# main.net
KiCad netlist of a schematic drawn in EAGLE
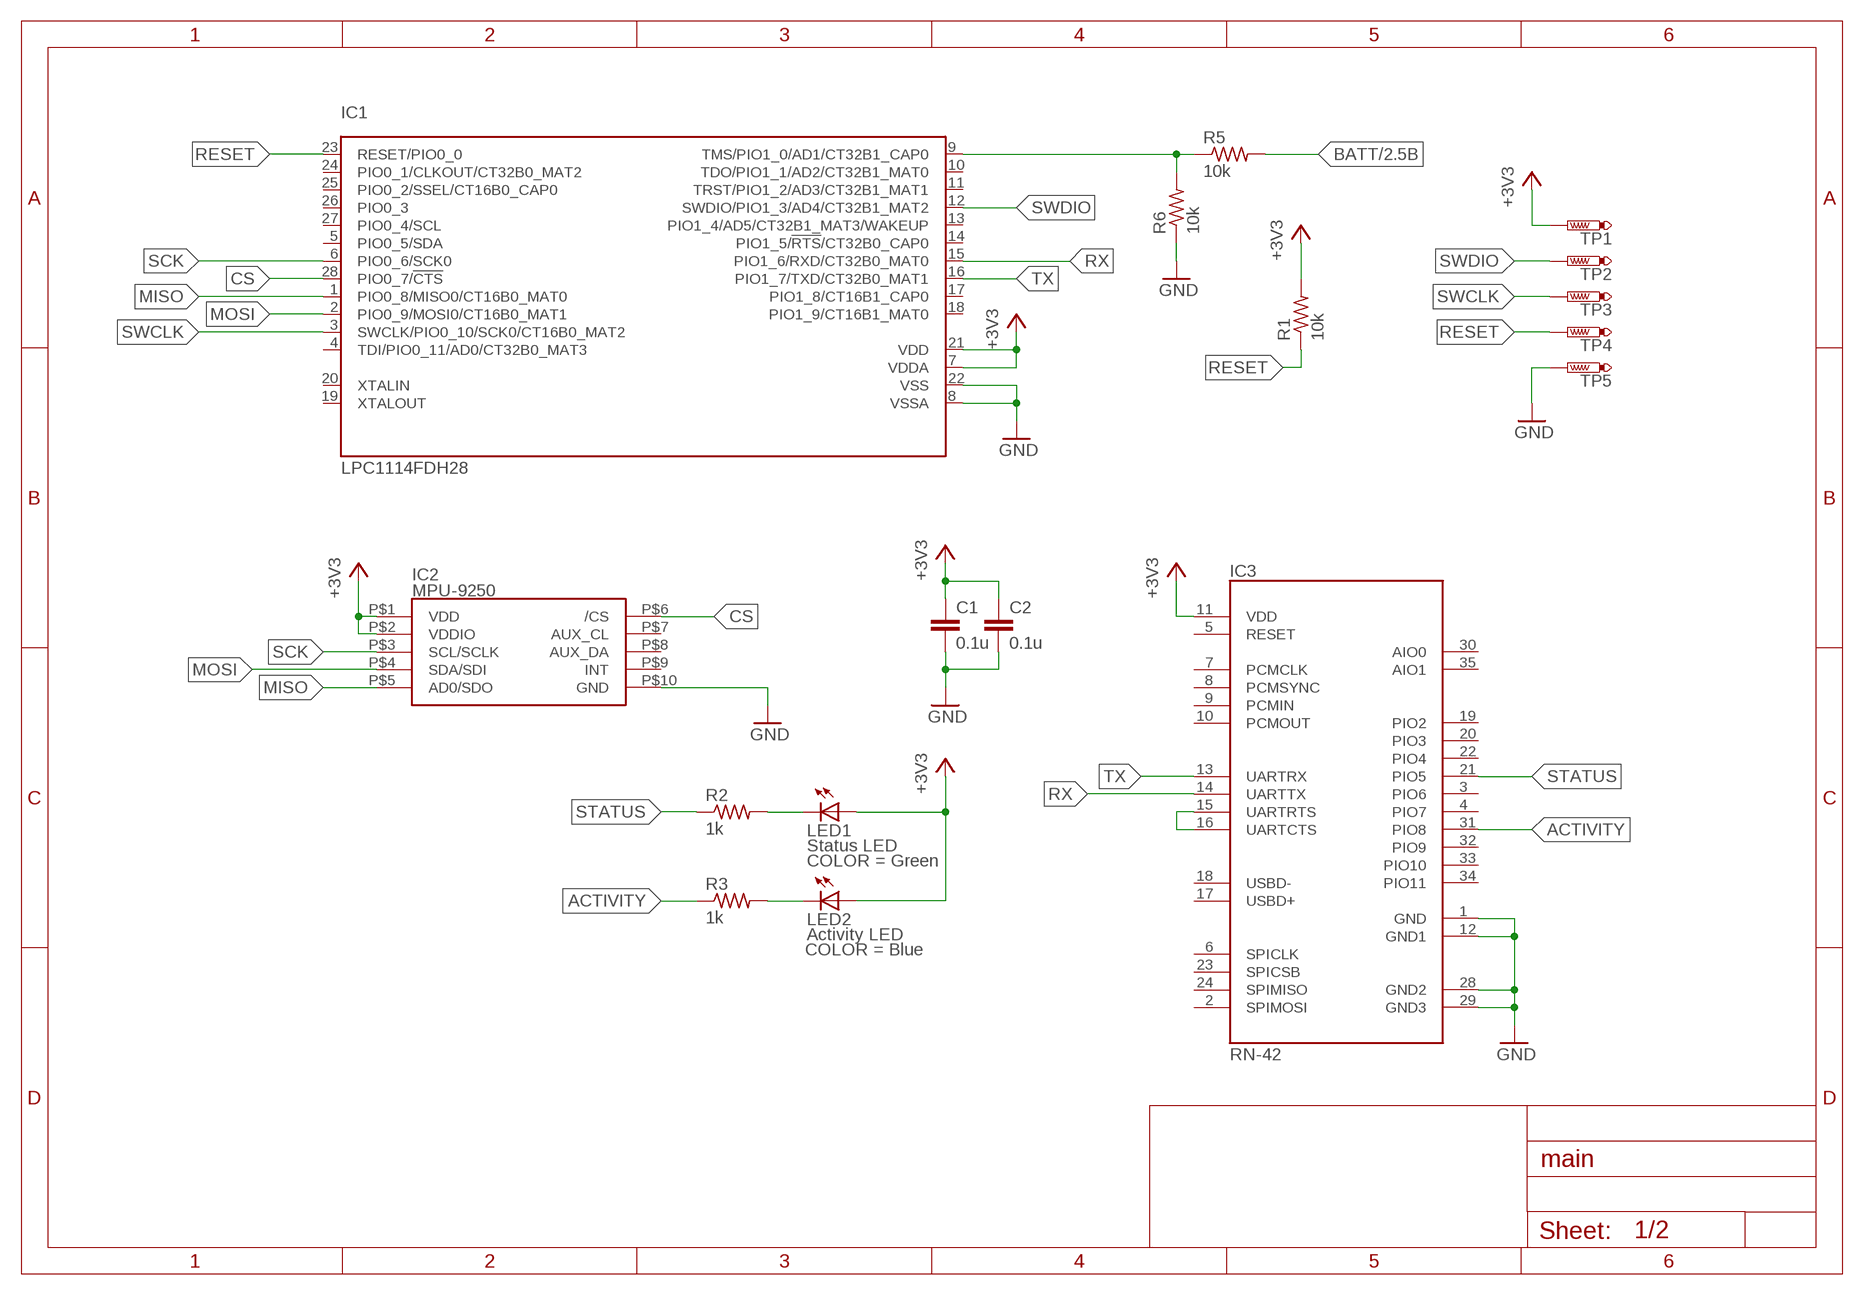
[diagram p0: schematic, sheet 1]
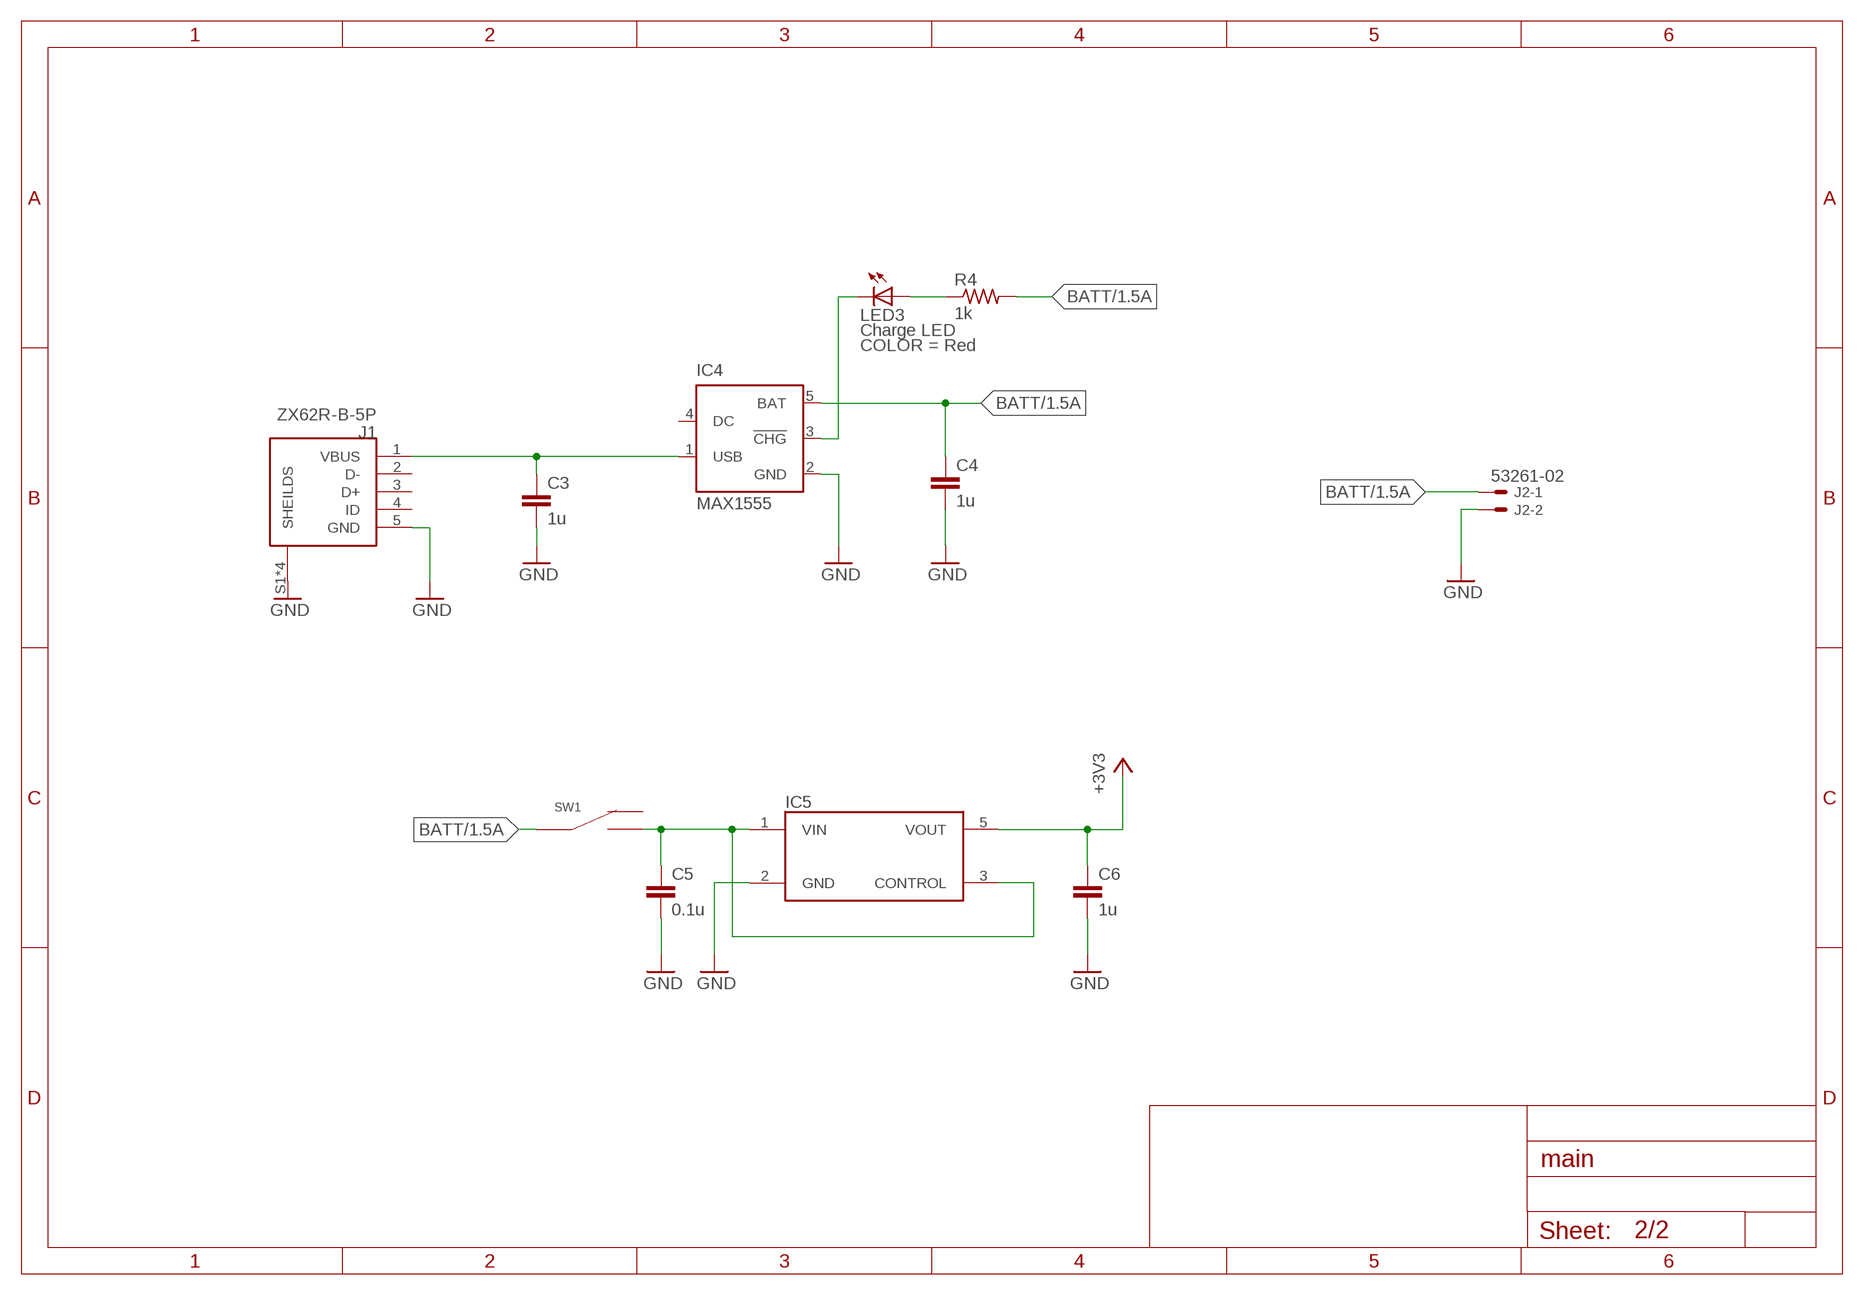
[diagram p1: schematic, sheet 2]

(export (version "E")
  (design (tool "Eeschema 10.0.6"))
  (components
    (comp (ref "C3")
      (value "1u")
      (footprint "eagle-import:C0603")
      (libsource (lib "eagle-import") (part "C-EUC0603"))
    )
    (comp (ref "C4")
      (value "1u")
      (footprint "eagle-import:C0603")
      (libsource (lib "eagle-import") (part "C-EUC0603"))
    )
    (comp (ref "C5")
      (value "0.1u")
      (footprint "eagle-import:C0603")
      (libsource (lib "eagle-import") (part "C-EUC0603"))
    )
    (comp (ref "C6")
      (value "1u")
      (footprint "eagle-import:C0603")
      (libsource (lib "eagle-import") (part "C-EUC0603"))
    )
    (comp (ref "IC4")
      (value "MAX1555")
      (footprint "eagle-import:SOT23-5L")
      (fields (field (name "MF") "MAXIM") (field (name "MPN") "MAX1555EZK+T"))
      (libsource (lib "eagle-import") (part "MAX1555"))
    )
    (comp (ref "IC5")
      (value "NJM2866F33")
      (footprint "eagle-import:SOT23-5L")
      (fields (field (name "MF") "NewJRC"))
      (libsource (lib "eagle-import") (part "NJM2866F33"))
    )
    (comp (ref "J1")
      (value "ZX62R-B-5P")
      (footprint "eagle-import:ZX62R-B-5P")
      (fields (field (name "MF") "Hirose"))
      (libsource (lib "eagle-import") (part "ZX62R-B-5P"))
    )
    (comp (ref "J2")
      (value "53261-02")
      (footprint "eagle-import:53261-02")
      (fields
        (field (name "MF") "Molex")
        (field (name "MPN") "53261-0271")
        (field (name "OC") "542-7090")
        (field (name "SITE") "RS Components")
      )
      (libsource (lib "eagle-import") (part "53?-02261"))
    )
    (comp (ref "LED3")
      (value "Charge LED")
      (footprint "eagle-import:CHIP-LED0603")
      (fields
        (field (name "COLOR") "Red")
        (field (name "MF") "OptoSupply")
        (field (name "MPN") "OSHR1608C1A")
      )
      (libsource (lib "eagle-import") (part "LEDCHIP-LED0603"))
    )
    (comp (ref "R4")
      (value "1k")
      (footprint "eagle-import:R0603")
      (libsource (lib "eagle-import") (part "R-US_R0603"))
    )
    (comp (ref "SW1")
      (value "SK-12D01-VG4")
      (footprint "eagle-import:SK-12D01-VG4")
      (fields (field (name "MF") "Zhejiang Jianfu"))
      (libsource (lib "eagle-import") (part "SK-12D01-VG4"))
    )
    (comp (ref "C1")
      (value "0.1u")
      (footprint "eagle-import:C0603")
      (libsource (lib "eagle-import") (part "C-EUC0603"))
    )
    (comp (ref "C2")
      (value "0.1u")
      (footprint "eagle-import:C0603")
      (libsource (lib "eagle-import") (part "C-EUC0603"))
    )
    (comp (ref "IC1")
      (value "LPC1114FDH28")
      (footprint "eagle-import:SOT361-1")
      (fields (field (name "MF") "NXP Semiconductors") (field (name "MPN") "LPC1114FDH28/102"))
      (libsource (lib "eagle-import") (part "LPC1114FDH28"))
    )
    (comp (ref "IC2")
      (value "MPU-9250")
      (footprint "eagle-import:DIP10S")
      (fields (field (name "MF") "InverSense"))
      (libsource (lib "eagle-import") (part "MPU-9250"))
    )
    (comp (ref "IC3")
      (value "RN-42")
      (footprint "eagle-import:RN41")
      (fields (field (name "MF") "Microchip") (field (name "MPN") "RN-42-I/RM"))
      (libsource (lib "eagle-import") (part "BLUETOOTH-RN41{dblquote}"))
    )
    (comp (ref "LED1")
      (value "Status LED")
      (footprint "eagle-import:CHIP-LED0603")
      (fields
        (field (name "COLOR") "Green")
        (field (name "MF") "OptoSupply")
        (field (name "MPN") "OSYG1608C1A")
      )
      (libsource (lib "eagle-import") (part "LEDCHIP-LED0603"))
    )
    (comp (ref "LED2")
      (value "Activity LED")
      (footprint "eagle-import:CHIP-LED0603")
      (fields
        (field (name "COLOR") "Blue")
        (field (name "MF") "OptoSupply")
        (field (name "MPN") "OSBL1608C1A")
      )
      (libsource (lib "eagle-import") (part "LEDCHIP-LED0603"))
    )
    (comp (ref "R1")
      (value "10k")
      (footprint "eagle-import:R0603")
      (libsource (lib "eagle-import") (part "R-US_R0603"))
    )
    (comp (ref "R2")
      (value "1k")
      (footprint "eagle-import:R0603")
      (libsource (lib "eagle-import") (part "R-US_R0603"))
    )
    (comp (ref "R3")
      (value "1k")
      (footprint "eagle-import:R0603")
      (libsource (lib "eagle-import") (part "R-US_R0603"))
    )
    (comp (ref "R5")
      (value "10k")
      (footprint "eagle-import:R0603")
      (libsource (lib "eagle-import") (part "R-US_R0603"))
    )
    (comp (ref "R6")
      (value "10k")
      (footprint "eagle-import:R0603")
      (libsource (lib "eagle-import") (part "R-US_R0603"))
    )
    (comp (ref "TP1")
      (value "3V3")
      (footprint "eagle-import:B1,27")
      (libsource (lib "eagle-import") (part "PTR1B1,27"))
    )
    (comp (ref "TP2")
      (value "SWDIO")
      (footprint "eagle-import:B1,27")
      (libsource (lib "eagle-import") (part "PTR1B1,27"))
    )
    (comp (ref "TP3")
      (value "SWCLK")
      (footprint "eagle-import:B1,27")
      (libsource (lib "eagle-import") (part "PTR1B1,27"))
    )
    (comp (ref "TP4")
      (value "RESET")
      (footprint "eagle-import:B1,27")
      (libsource (lib "eagle-import") (part "PTR1B1,27"))
    )
    (comp (ref "TP5")
      (value "GND")
      (footprint "eagle-import:B1,27")
      (libsource (lib "eagle-import") (part "PTR1B1,27"))
    )
  )
  (nets
    (net (code "1") (name "+3V3") (class "Default")
      (node (ref "C1") (pin "1") (pinfunction "1_1") (pintype "passive"))
      (node (ref "C2") (pin "1") (pinfunction "1_1") (pintype "passive"))
      (node (ref "C6") (pin "1") (pinfunction "1_1") (pintype "passive"))
      (node (ref "IC1") (pin "21") (pinfunction "VDD_21") (pintype "power_in"))
      (node (ref "IC1") (pin "7") (pinfunction "VDDA_7") (pintype "power_in"))
      (node (ref "IC2") (pin "P$1") (pinfunction "VDD_P$1") (pintype "bidirectional"))
      (node (ref "IC2") (pin "P$2") (pinfunction "VDDIO_P$2") (pintype "bidirectional"))
      (node (ref "IC3") (pin "11") (pinfunction "VDD_11") (pintype "bidirectional"))
      (node (ref "IC5") (pin "5") (pinfunction "VOUT_5") (pintype "bidirectional"))
      (node (ref "LED1") (pin "A") (pinfunction "A_A") (pintype "passive"))
      (node (ref "LED2") (pin "A") (pinfunction "A_A") (pintype "passive"))
      (node (ref "R1") (pin "2") (pinfunction "2_2") (pintype "passive"))
      (node (ref "TP1") (pin "TP") (pinfunction "TP_TP") (pintype "input"))
    )
    (net (code "2") (name "ACTIVITY") (class "Default")
      (node (ref "IC3") (pin "31") (pinfunction "PIO8_31") (pintype "bidirectional"))
      (node (ref "R3") (pin "1") (pinfunction "1_1") (pintype "passive"))
    )
    (net (code "3") (name "BATT") (class "Default")
      (node (ref "C4") (pin "1") (pinfunction "1_1") (pintype "passive"))
      (node (ref "IC4") (pin "5") (pinfunction "BAT_5") (pintype "passive"))
      (node (ref "J2") (pin "1") (pinfunction "S_1") (pintype "passive"))
      (node (ref "R4") (pin "2") (pinfunction "2_2") (pintype "passive"))
      (node (ref "R5") (pin "2") (pinfunction "2_2") (pintype "passive"))
      (node (ref "SW1") (pin "P$2") (pinfunction "P$1_P$2") (pintype "bidirectional"))
    )
    (net (code "4") (name "CS") (class "Default")
      (node (ref "IC1") (pin "28") (pinfunction "PIO0_7/~{CTS}_28") (pintype "bidirectional"))
      (node (ref "IC2") (pin "P$6") (pinfunction "/CS_P$6") (pintype "bidirectional"))
    )
    (net (code "5") (name "GND") (class "Default")
      (node (ref "C1") (pin "2") (pinfunction "2_2") (pintype "passive"))
      (node (ref "C2") (pin "2") (pinfunction "2_2") (pintype "passive"))
      (node (ref "C3") (pin "2") (pinfunction "2_2") (pintype "passive"))
      (node (ref "C4") (pin "2") (pinfunction "2_2") (pintype "passive"))
      (node (ref "C5") (pin "2") (pinfunction "2_2") (pintype "passive"))
      (node (ref "C6") (pin "2") (pinfunction "2_2") (pintype "passive"))
      (node (ref "IC1") (pin "22") (pinfunction "VSS_22") (pintype "power_in"))
      (node (ref "IC1") (pin "8") (pinfunction "VSSA_8") (pintype "power_in"))
      (node (ref "IC2") (pin "P$10") (pinfunction "GND_P$10") (pintype "bidirectional"))
      (node (ref "IC3") (pin "1") (pinfunction "GND_1") (pintype "bidirectional"))
      (node (ref "IC3") (pin "12") (pinfunction "GND1_12") (pintype "bidirectional"))
      (node (ref "IC3") (pin "28") (pinfunction "GND2_28") (pintype "bidirectional"))
      (node (ref "IC3") (pin "29") (pinfunction "GND3_29") (pintype "bidirectional"))
      (node (ref "IC4") (pin "2") (pinfunction "GND_2") (pintype "power_in"))
      (node (ref "IC5") (pin "2") (pinfunction "GND_2") (pintype "bidirectional"))
      (node (ref "J1") (pin "5") (pinfunction "GND_5") (pintype "bidirectional"))
      (node (ref "J1") (pin "S1") (pinfunction "SHEILDS_S1") (pintype "bidirectional"))
      (node (ref "J1") (pin "S2") (pinfunction "SHEILDS_S2") (pintype "bidirectional"))
      (node (ref "J1") (pin "S3") (pinfunction "SHEILDS_S3") (pintype "bidirectional"))
      (node (ref "J1") (pin "S4") (pinfunction "SHEILDS_S4") (pintype "bidirectional"))
      (node (ref "J2") (pin "2") (pinfunction "S_2") (pintype "passive"))
      (node (ref "R6") (pin "1") (pinfunction "1_1") (pintype "passive"))
      (node (ref "TP5") (pin "TP") (pinfunction "TP_TP") (pintype "input"))
    )
    (net (code "6") (name "MISO") (class "Default")
      (node (ref "IC1") (pin "1") (pinfunction "PIO0_8/MISO0/CT16B0_MAT0_1") (pintype "bidirectional"))
      (node (ref "IC2") (pin "P$5") (pinfunction "AD0/SDO_P$5") (pintype "bidirectional"))
    )
    (net (code "7") (name "MOSI") (class "Default")
      (node (ref "IC1") (pin "2") (pinfunction "PIO0_9/MOSI0/CT16B0_MAT1_2") (pintype "bidirectional"))
      (node (ref "IC2") (pin "P$4") (pinfunction "SDA/SDI_P$4") (pintype "bidirectional"))
    )
    (net (code "8") (name "Net-(IC1-TMS{slash}PIO1_0{slash}AD1{slash}CT32B1_CAP0)") (class "Default")
      (node (ref "IC1") (pin "9") (pinfunction "TMS/PIO1_0/AD1/CT32B1_CAP0_9") (pintype "bidirectional"))
      (node (ref "R5") (pin "1") (pinfunction "1_1") (pintype "passive"))
      (node (ref "R6") (pin "2") (pinfunction "2_2") (pintype "passive"))
    )
    (net (code "9") (name "Net-(IC3-UARTCTS)") (class "Default")
      (node (ref "IC3") (pin "15") (pinfunction "UARTRTS_15") (pintype "bidirectional"))
      (node (ref "IC3") (pin "16") (pinfunction "UARTCTS_16") (pintype "bidirectional"))
    )
    (net (code "10") (name "Net-(IC4-USB)") (class "Default")
      (node (ref "C3") (pin "1") (pinfunction "1_1") (pintype "passive"))
      (node (ref "IC4") (pin "1") (pinfunction "USB_1") (pintype "input"))
      (node (ref "J1") (pin "1") (pinfunction "VBUS_1") (pintype "bidirectional"))
    )
    (net (code "11") (name "Net-(IC4-~{CHG})") (class "Default")
      (node (ref "IC4") (pin "3") (pinfunction "~{CHG}_3") (pintype "output"))
      (node (ref "LED3") (pin "C") (pinfunction "C_C") (pintype "passive"))
    )
    (net (code "12") (name "Net-(IC5-CONTROL)") (class "Default")
      (node (ref "C5") (pin "1") (pinfunction "1_1") (pintype "passive"))
      (node (ref "IC5") (pin "1") (pinfunction "VIN_1") (pintype "bidirectional"))
      (node (ref "IC5") (pin "3") (pinfunction "CONTROL_3") (pintype "bidirectional"))
      (node (ref "SW1") (pin "P$3") (pinfunction "P$3_P$3") (pintype "bidirectional"))
    )
    (net (code "13") (name "Net-(LED1-PadC)") (class "Default")
      (node (ref "LED1") (pin "C") (pinfunction "C_C") (pintype "passive"))
      (node (ref "R2") (pin "2") (pinfunction "2_2") (pintype "passive"))
    )
    (net (code "14") (name "Net-(LED2-PadC)") (class "Default")
      (node (ref "LED2") (pin "C") (pinfunction "C_C") (pintype "passive"))
      (node (ref "R3") (pin "2") (pinfunction "2_2") (pintype "passive"))
    )
    (net (code "15") (name "Net-(LED3-PadA)") (class "Default")
      (node (ref "LED3") (pin "A") (pinfunction "A_A") (pintype "passive"))
      (node (ref "R4") (pin "1") (pinfunction "1_1") (pintype "passive"))
    )
    (net (code "16") (name "RESET") (class "Default")
      (node (ref "IC1") (pin "23") (pinfunction "RESET/PIO0_0_23") (pintype "bidirectional"))
      (node (ref "R1") (pin "1") (pinfunction "1_1") (pintype "passive"))
      (node (ref "TP4") (pin "TP") (pinfunction "TP_TP") (pintype "input"))
    )
    (net (code "17") (name "RX") (class "Default")
      (node (ref "IC1") (pin "15") (pinfunction "PIO1_6/RXD/CT32B0_MAT0_15") (pintype "bidirectional"))
      (node (ref "IC3") (pin "14") (pinfunction "UARTTX_14") (pintype "bidirectional"))
    )
    (net (code "18") (name "SCK") (class "Default")
      (node (ref "IC1") (pin "6") (pinfunction "PIO0_6/SCK0_6") (pintype "bidirectional"))
      (node (ref "IC2") (pin "P$3") (pinfunction "SCL/SCLK_P$3") (pintype "bidirectional"))
    )
    (net (code "19") (name "STATUS") (class "Default")
      (node (ref "IC3") (pin "21") (pinfunction "PIO5_21") (pintype "bidirectional"))
      (node (ref "R2") (pin "1") (pinfunction "1_1") (pintype "passive"))
    )
    (net (code "20") (name "SWCLK") (class "Default")
      (node (ref "IC1") (pin "3") (pinfunction "SWCLK/PIO0_10/SCK0/CT16B0_MAT2_3") (pintype "bidirectional"))
      (node (ref "TP3") (pin "TP") (pinfunction "TP_TP") (pintype "input"))
    )
    (net (code "21") (name "SWDIO") (class "Default")
      (node (ref "IC1") (pin "12") (pinfunction "SWDIO/PIO1_3/AD4/CT32B1_MAT2_12") (pintype "bidirectional"))
      (node (ref "TP2") (pin "TP") (pinfunction "TP_TP") (pintype "input"))
    )
    (net (code "22") (name "TX") (class "Default")
      (node (ref "IC1") (pin "16") (pinfunction "PIO1_7/TXD/CT32B0_MAT1_16") (pintype "bidirectional"))
      (node (ref "IC3") (pin "13") (pinfunction "UARTRX_13") (pintype "bidirectional"))
    )
    (net (code "23") (name "unconnected-(IC1-PIO0_1{slash}CLKOUT{slash}CT32B0_MAT2-Pad24)") (class "Default")
      (node (ref "IC1") (pin "24") (pinfunction "PIO0_1/CLKOUT/CT32B0_MAT2_24") (pintype "bidirectional"))
    )
    (net (code "24") (name "unconnected-(IC1-PIO0_2{slash}SSEL{slash}CT16B0_CAP0-Pad25)") (class "Default")
      (node (ref "IC1") (pin "25") (pinfunction "PIO0_2/SSEL/CT16B0_CAP0_25") (pintype "bidirectional"))
    )
    (net (code "25") (name "unconnected-(IC1-PIO0_3-Pad26)") (class "Default")
      (node (ref "IC1") (pin "26") (pinfunction "PIO0_3_26") (pintype "bidirectional"))
    )
    (net (code "26") (name "unconnected-(IC1-PIO0_4{slash}SCL-Pad27)") (class "Default")
      (node (ref "IC1") (pin "27") (pinfunction "PIO0_4/SCL_27") (pintype "bidirectional"))
    )
    (net (code "27") (name "unconnected-(IC1-PIO0_5{slash}SDA-Pad5)") (class "Default")
      (node (ref "IC1") (pin "5") (pinfunction "PIO0_5/SDA_5") (pintype "bidirectional"))
    )
    (net (code "28") (name "unconnected-(IC1-PIO1_4{slash}AD5{slash}CT32B1_MAT3{slash}WAKEUP-Pad13)") (class "Default")
      (node (ref "IC1") (pin "13") (pinfunction "PIO1_4/AD5/CT32B1_MAT3/WAKEUP_13") (pintype "bidirectional"))
    )
    (net (code "29") (name "unconnected-(IC1-PIO1_5{slash}~{RTS}{slash}CT32B0_CAP0-Pad14)") (class "Default")
      (node (ref "IC1") (pin "14") (pinfunction "PIO1_5/~{RTS}/CT32B0_CAP0_14") (pintype "bidirectional"))
    )
    (net (code "30") (name "unconnected-(IC1-PIO1_8{slash}CT16B1_CAP0-Pad17)") (class "Default")
      (node (ref "IC1") (pin "17") (pinfunction "PIO1_8/CT16B1_CAP0_17") (pintype "bidirectional"))
    )
    (net (code "31") (name "unconnected-(IC1-PIO1_9{slash}CT16B1_MAT0-Pad18)") (class "Default")
      (node (ref "IC1") (pin "18") (pinfunction "PIO1_9/CT16B1_MAT0_18") (pintype "bidirectional"))
    )
    (net (code "32") (name "unconnected-(IC1-TDI{slash}PIO0_11{slash}AD0{slash}CT32B0_MAT3-Pad4)") (class "Default")
      (node (ref "IC1") (pin "4") (pinfunction "TDI/PIO0_11/AD0/CT32B0_MAT3_4") (pintype "bidirectional"))
    )
    (net (code "33") (name "unconnected-(IC1-TDO{slash}PIO1_1{slash}AD2{slash}CT32B1_MAT0-Pad10)") (class "Default")
      (node (ref "IC1") (pin "10") (pinfunction "TDO/PIO1_1/AD2/CT32B1_MAT0_10") (pintype "bidirectional"))
    )
    (net (code "34") (name "unconnected-(IC1-TRST{slash}PIO1_2{slash}AD3{slash}CT32B1_MAT1-Pad11)") (class "Default")
      (node (ref "IC1") (pin "11") (pinfunction "TRST/PIO1_2/AD3/CT32B1_MAT1_11") (pintype "bidirectional"))
    )
    (net (code "35") (name "unconnected-(IC1-XTALIN-Pad20)") (class "Default")
      (node (ref "IC1") (pin "20") (pinfunction "XTALIN_20") (pintype "input"))
    )
    (net (code "36") (name "unconnected-(IC1-XTALOUT-Pad19)") (class "Default")
      (node (ref "IC1") (pin "19") (pinfunction "XTALOUT_19") (pintype "output"))
    )
    (net (code "37") (name "unconnected-(IC2-AUX_CL-PadP$7)") (class "Default")
      (node (ref "IC2") (pin "P$7") (pinfunction "AUX_CL_P$7") (pintype "bidirectional"))
    )
    (net (code "38") (name "unconnected-(IC2-AUX_DA-PadP$8)") (class "Default")
      (node (ref "IC2") (pin "P$8") (pinfunction "AUX_DA_P$8") (pintype "bidirectional"))
    )
    (net (code "39") (name "unconnected-(IC2-INT-PadP$9)") (class "Default")
      (node (ref "IC2") (pin "P$9") (pinfunction "INT_P$9") (pintype "bidirectional"))
    )
    (net (code "40") (name "unconnected-(IC3-AIO0-Pad30)") (class "Default")
      (node (ref "IC3") (pin "30") (pinfunction "AIO0_30") (pintype "bidirectional"))
    )
    (net (code "41") (name "unconnected-(IC3-AIO1-Pad35)") (class "Default")
      (node (ref "IC3") (pin "35") (pinfunction "AIO1_35") (pintype "bidirectional"))
    )
    (net (code "42") (name "unconnected-(IC3-PCMCLK-Pad7)") (class "Default")
      (node (ref "IC3") (pin "7") (pinfunction "PCMCLK_7") (pintype "bidirectional"))
    )
    (net (code "43") (name "unconnected-(IC3-PCMIN-Pad9)") (class "Default")
      (node (ref "IC3") (pin "9") (pinfunction "PCMIN_9") (pintype "bidirectional"))
    )
    (net (code "44") (name "unconnected-(IC3-PCMOUT-Pad10)") (class "Default")
      (node (ref "IC3") (pin "10") (pinfunction "PCMOUT_10") (pintype "bidirectional"))
    )
    (net (code "45") (name "unconnected-(IC3-PCMSYNC-Pad8)") (class "Default")
      (node (ref "IC3") (pin "8") (pinfunction "PCMSYNC_8") (pintype "bidirectional"))
    )
    (net (code "46") (name "unconnected-(IC3-PIO2-Pad19)") (class "Default")
      (node (ref "IC3") (pin "19") (pinfunction "PIO2_19") (pintype "bidirectional"))
    )
    (net (code "47") (name "unconnected-(IC3-PIO3-Pad20)") (class "Default")
      (node (ref "IC3") (pin "20") (pinfunction "PIO3_20") (pintype "bidirectional"))
    )
    (net (code "48") (name "unconnected-(IC3-PIO4-Pad22)") (class "Default")
      (node (ref "IC3") (pin "22") (pinfunction "PIO4_22") (pintype "bidirectional"))
    )
    (net (code "49") (name "unconnected-(IC3-PIO6-Pad3)") (class "Default")
      (node (ref "IC3") (pin "3") (pinfunction "PIO6_3") (pintype "bidirectional"))
    )
    (net (code "50") (name "unconnected-(IC3-PIO7-Pad4)") (class "Default")
      (node (ref "IC3") (pin "4") (pinfunction "PIO7_4") (pintype "bidirectional"))
    )
    (net (code "51") (name "unconnected-(IC3-PIO9-Pad32)") (class "Default")
      (node (ref "IC3") (pin "32") (pinfunction "PIO9_32") (pintype "bidirectional"))
    )
    (net (code "52") (name "unconnected-(IC3-PIO10-Pad33)") (class "Default")
      (node (ref "IC3") (pin "33") (pinfunction "PIO10_33") (pintype "bidirectional"))
    )
    (net (code "53") (name "unconnected-(IC3-PIO11-Pad34)") (class "Default")
      (node (ref "IC3") (pin "34") (pinfunction "PIO11_34") (pintype "bidirectional"))
    )
    (net (code "54") (name "unconnected-(IC3-RESET-Pad5)") (class "Default")
      (node (ref "IC3") (pin "5") (pinfunction "RESET_5") (pintype "bidirectional"))
    )
    (net (code "55") (name "unconnected-(IC3-SPICLK-Pad6)") (class "Default")
      (node (ref "IC3") (pin "6") (pinfunction "SPICLK_6") (pintype "bidirectional"))
    )
    (net (code "56") (name "unconnected-(IC3-SPICSB-Pad23)") (class "Default")
      (node (ref "IC3") (pin "23") (pinfunction "SPICSB_23") (pintype "bidirectional"))
    )
    (net (code "57") (name "unconnected-(IC3-SPIMISO-Pad24)") (class "Default")
      (node (ref "IC3") (pin "24") (pinfunction "SPIMISO_24") (pintype "bidirectional"))
    )
    (net (code "58") (name "unconnected-(IC3-SPIMOSI-Pad2)") (class "Default")
      (node (ref "IC3") (pin "2") (pinfunction "SPIMOSI_2") (pintype "bidirectional"))
    )
    (net (code "59") (name "unconnected-(IC3-USBD+-Pad17)") (class "Default")
      (node (ref "IC3") (pin "17") (pinfunction "USBD+_17") (pintype "bidirectional"))
    )
    (net (code "60") (name "unconnected-(IC3-USBD--Pad18)") (class "Default")
      (node (ref "IC3") (pin "18") (pinfunction "USBD-_18") (pintype "bidirectional"))
    )
    (net (code "61") (name "unconnected-(IC4-DC-Pad4)") (class "Default")
      (node (ref "IC4") (pin "4") (pinfunction "DC_4") (pintype "input"))
    )
    (net (code "62") (name "unconnected-(J1-D+-Pad3)") (class "Default")
      (node (ref "J1") (pin "3") (pinfunction "D+_3") (pintype "bidirectional"))
    )
    (net (code "63") (name "unconnected-(J1-D--Pad2)") (class "Default")
      (node (ref "J1") (pin "2") (pinfunction "D-_2") (pintype "bidirectional"))
    )
    (net (code "64") (name "unconnected-(J1-ID-Pad4)") (class "Default")
      (node (ref "J1") (pin "4") (pinfunction "ID_4") (pintype "bidirectional"))
    )
    (net (code "65") (name "unconnected-(SW1-P$2-PadP$1)") (class "Default")
      (node (ref "SW1") (pin "P$1") (pinfunction "P$2_P$1") (pintype "bidirectional"))
    )
  )
)
